# pca20020_sheet7_sound_and_light.net
KiCad netlist of a schematic drawn in Altium Designer
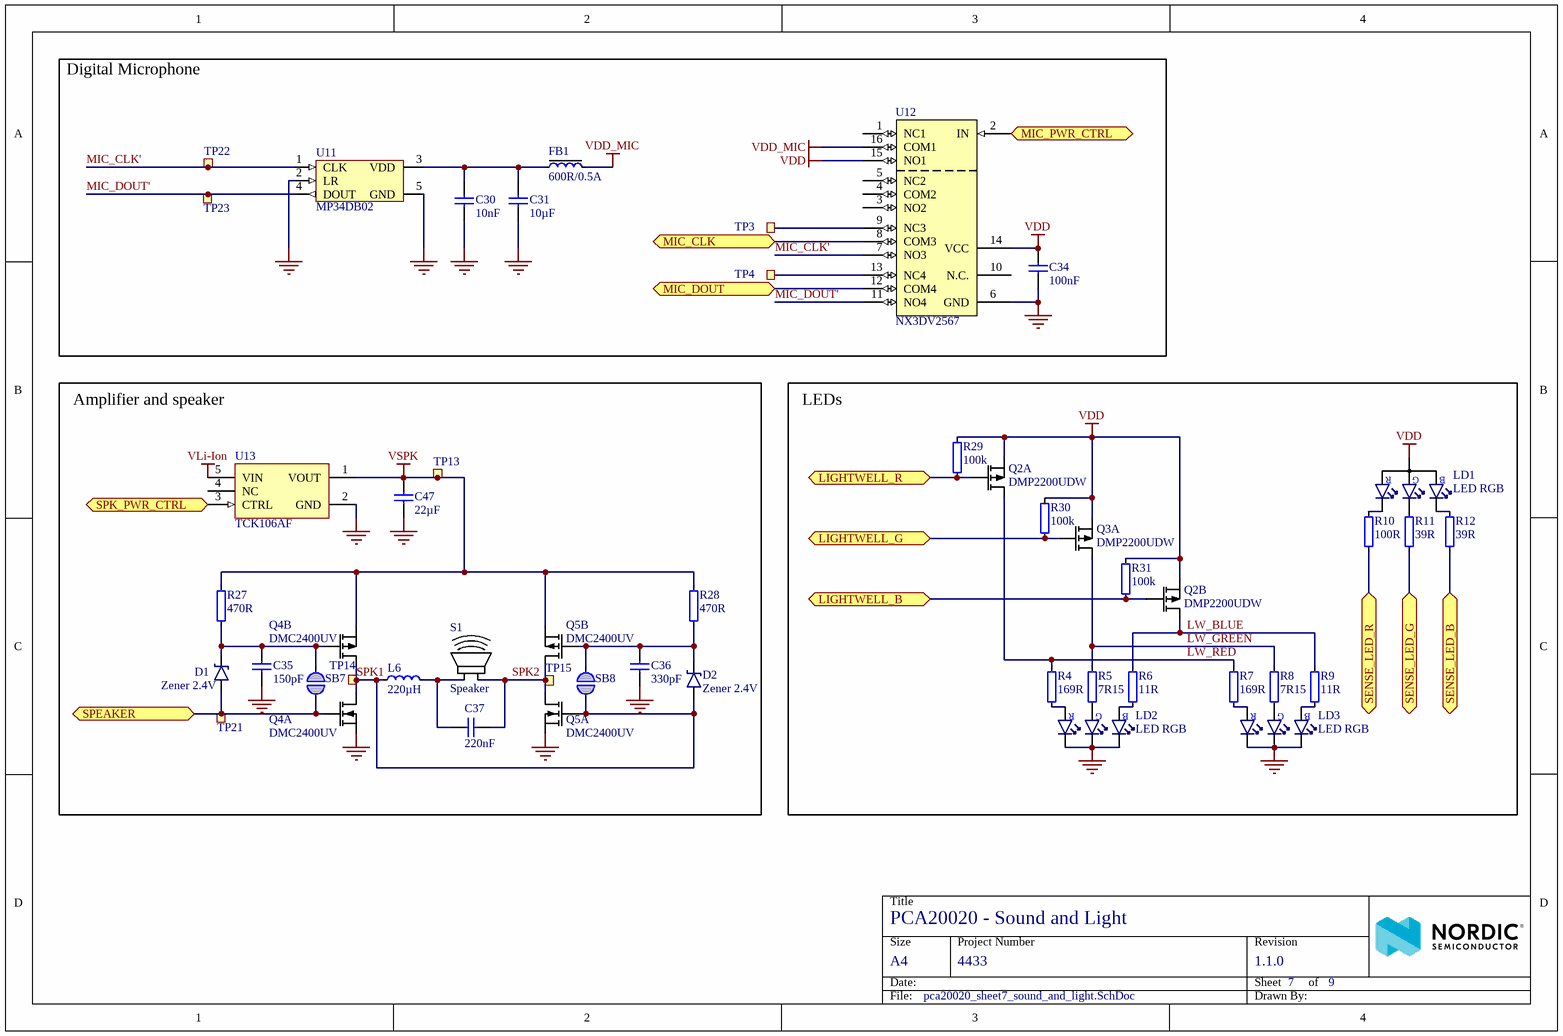
[diagram p0: pca20020_sheet7_sound_and_light.SchDoc]

(export (version "E")
  (design (tool "Eeschema 10.0.6"))
  (components
    (comp (ref "C30")
      (value "10nF")
      (footprint "CAPC1005X04L")
      (description "Capacitor, X7R, ±10%")
      (fields (field (name "PART NUMBER") "C0402-10n") (field (name "PUBLISHER") "Nordic Semiconductor"))
      (libsource (lib "Nordic Passive DB") (part "CAP"))
    )
    (comp (ref "C31")
      (value "10µF")
      (footprint "CAPC1608X06L")
      (description "Capacitor, X5R, ±20%")
      (fields (field (name "PART NUMBER") "C0603-10µ") (field (name "PUBLISHER") "Nordic Semiconductor"))
      (libsource (lib "Nordic Passive DB") (part "CAP"))
    )
    (comp (ref "C34")
      (value "100nF")
      (footprint "CAPC1005X04L")
      (description "Capacitor, X7R, ±10%")
      (fields (field (name "PART NUMBER") "C0402-100n") (field (name "PUBLISHER") "Nordic Semiconductor"))
      (libsource (lib "Nordic Passive DB") (part "CAP"))
    )
    (comp (ref "C35")
      (value "150pF")
      (footprint "CAPC1005X04L")
      (description "Capacitor, NP0, ±5%")
      (fields (field (name "PART NUMBER") "C0402-150p") (field (name "PUBLISHER") "Nordic Semiconductor"))
      (libsource (lib "Nordic Passive DB") (part "CAP"))
    )
    (comp (ref "C36")
      (value "330pF")
      (footprint "CAPC1005X04L")
      (description "Capacitor, NP0, ±5%")
      (fields (field (name "PART NUMBER") "C0402-330p") (field (name "PUBLISHER") "Nordic Semiconductor"))
      (libsource (lib "Nordic Passive DB") (part "CAP"))
    )
    (comp (ref "C37")
      (value "220nF")
      (footprint "CAPC1005X04L")
      (description "Capacitor, X7R, ±10%")
      (fields (field (name "PART NUMBER") "C0402-220n") (field (name "PUBLISHER") "Nordic Semiconductor"))
      (libsource (lib "Nordic Passive DB") (part "CAP"))
    )
    (comp (ref "C47")
      (value "22µF")
      (footprint "CAPC1608X06L")
      (description "CAP CER 22UF 6.3V 20% X5R 0603")
      (fields
        (field (name "PART NUMBER") "C0603-22µ-6.3V")
        (field (name "MANUFACTURER") "Samsung")
        (field (name "PUBLISHER") "Nordic Semiconductor")
      )
      (libsource (lib "Nordic Passive DB") (part "CAP"))
    )
    (comp (ref "D1")
      (value "Zener 2.4V")
      (footprint "SOD-523")
      (description "Diode, Zener, 2.4V, 0.3W")
      (fields
        (field (name "PART NUMBER") "BZT52C2V4T")
        (field (name "MANUFACTURER") "Diodes Incorporated")
        (field (name "PUBLISHER") "Nordic Semiconductor")
      )
      (libsource (lib "Nordic Discrete DB") (part "D{colon}ZENER"))
    )
    (comp (ref "D2")
      (value "Zener 2.4V")
      (footprint "SOD-523")
      (description "Diode, Zener, 2.4V, 0.3W")
      (fields
        (field (name "PART NUMBER") "BZT52C2V4T")
        (field (name "MANUFACTURER") "Diodes Incorporated")
        (field (name "PUBLISHER") "Nordic Semiconductor")
      )
      (libsource (lib "Nordic Discrete DB") (part "D{colon}ZENER"))
    )
    (comp (ref "FB1")
      (value "600R/0.5A")
      (footprint "INDC1608X06L")
      (description "Ferrite Bead, 600 Ohm @ 100MHz, 500mA, 380 mOhm Max")
      (fields
        (field (name "PART NUMBER") "FB0603-600R@100MHz-500mA")
        (field (name "MANUFACTURER") "Murata")
        (field (name "PUBLISHER") "Nordic Semiconductor")
      )
      (libsource (lib "Nordic Passive DB") (part "IND_F"))
    )
    (comp (ref "L6")
      (value "220µH")
      (footprint "INDP4040X25N")
      (description "Inductor, ±20%, 200mA, 2.76 Ohm")
      (fields
        (field (name "PART NUMBER") "L4040-220µ")
        (field (name "MANUFACTURER") "Bourns")
        (field (name "PUBLISHER") "Nordic Semiconductor")
      )
      (libsource (lib "Nordic Passive DB") (part "IND"))
    )
    (comp (ref "LD1")
      (value "LED RGB")
      (footprint "LED_RGB_0606")
      (description "RGB LED 1.60 mm x 1.60 mm SMD")
      (fields
        (field (name "PART NUMBER") "LTST-C19HE1WT")
        (field (name "MANUFACTURER") "Lite-On Inc")
        (field (name "PUBLISHER") "Nordic Semiconductor")
      )
      (libsource (lib "Nordic Discrete DB") (part "D{colon}LED_RGB"))
    )
    (comp (ref "LD2")
      (value "LED RGB")
      (footprint "MSL0104")
      (description "High brightness, side view RGB LED")
      (fields
        (field (name "PART NUMBER") "MSL0104RGBU1")
        (field (name "MANUFACTURER") "ROHM")
        (field (name "PUBLISHER") "Nordic Semiconductor")
      )
      (libsource (lib "Nordic Discrete DB") (part "D{colon}LED_RGB_MSL0104"))
    )
    (comp (ref "LD3")
      (value "LED RGB")
      (footprint "MSL0104")
      (description "High brightness, side view RGB LED")
      (fields
        (field (name "PART NUMBER") "MSL0104RGBU1")
        (field (name "MANUFACTURER") "ROHM")
        (field (name "PUBLISHER") "Nordic Semiconductor")
      )
      (libsource (lib "Nordic Discrete DB") (part "D{colon}LED_RGB_MSL0104"))
    )
    (comp (ref "Q2")
      (value "DMP2200UDW")
      (footprint "SOT-363")
      (description "Dual P Ch MOFET, 900mA, 260mOhm, 450mW")
      (fields
        (field (name "MANUFACTURER") "Diodes Incorporated")
        (field (name "PUBLISHER") "Nordic Semiconductor")
      )
      (libsource (lib "Nordic Discrete DB") (part "T{colon}FET-P-DUAL"))
    )
    (comp (ref "Q3")
      (value "DMP2200UDW")
      (footprint "SOT-363")
      (description "Dual P Ch MOFET, 900mA, 260mOhm, 450mW")
      (fields
        (field (name "MANUFACTURER") "Diodes Incorporated")
        (field (name "PUBLISHER") "Nordic Semiconductor")
      )
      (libsource (lib "Nordic Discrete DB") (part "T{colon}FET-P-DUAL"))
    )
    (comp (ref "Q4")
      (value "DMC2400UV")
      (footprint "SOTFL50P162X60-6N")
      (description "Dual N & P Ch MOFET, 1.03A/0.7A, 480mOhm, 450mW")
      (fields
        (field (name "MANUFACTURER") "Diodes Incorporated")
        (field (name "PUBLISHER") "Nordic Semiconductor")
      )
      (libsource (lib "Nordic Discrete DB") (part "T{colon}FET-N/P-DUAL"))
    )
    (comp (ref "Q5")
      (value "DMC2400UV")
      (footprint "SOTFL50P162X60-6N")
      (description "Dual N & P Ch MOFET, 1.03A/0.7A, 480mOhm, 450mW")
      (fields
        (field (name "MANUFACTURER") "Diodes Incorporated")
        (field (name "PUBLISHER") "Nordic Semiconductor")
      )
      (libsource (lib "Nordic Discrete DB") (part "T{colon}FET-N/P-DUAL"))
    )
    (comp (ref "R4")
      (value "169R")
      (footprint "RESC1005X04L")
      (description "Resistor, ±1%, 0.063W")
      (fields (field (name "PART NUMBER") "R0402-169") (field (name "PUBLISHER") "Nordic Semiconductor"))
      (libsource (lib "Nordic Passive DB") (part "RES_1"))
    )
    (comp (ref "R5")
      (value "7R15")
      (footprint "RESC1005X04L")
      (description "Resistor, ±1%, 0.063W")
      (fields (field (name "PART NUMBER") "R0402-7R15") (field (name "PUBLISHER") "Nordic Semiconductor"))
      (libsource (lib "Nordic Passive DB") (part "RES_1"))
    )
    (comp (ref "R6")
      (value "11R")
      (footprint "RESC1005X04L")
      (description "Resistor, ±1%, 0.063W")
      (fields (field (name "PART NUMBER") "R0402-11R") (field (name "PUBLISHER") "Nordic Semiconductor"))
      (libsource (lib "Nordic Passive DB") (part "RES_1"))
    )
    (comp (ref "R7")
      (value "169R")
      (footprint "RESC1005X04L")
      (description "Resistor, ±1%, 0.063W")
      (fields (field (name "PART NUMBER") "R0402-169") (field (name "PUBLISHER") "Nordic Semiconductor"))
      (libsource (lib "Nordic Passive DB") (part "RES_1"))
    )
    (comp (ref "R8")
      (value "7R15")
      (footprint "RESC1005X04L")
      (description "Resistor, ±1%, 0.063W")
      (fields (field (name "PART NUMBER") "R0402-7R15") (field (name "PUBLISHER") "Nordic Semiconductor"))
      (libsource (lib "Nordic Passive DB") (part "RES_1"))
    )
    (comp (ref "R9")
      (value "11R")
      (footprint "RESC1005X04L")
      (description "Resistor, ±1%, 0.063W")
      (fields (field (name "PART NUMBER") "R0402-11R") (field (name "PUBLISHER") "Nordic Semiconductor"))
      (libsource (lib "Nordic Passive DB") (part "RES_1"))
    )
    (comp (ref "R10")
      (value "100R")
      (footprint "RESC1005X04L")
      (description "Resistor, ±1%, 0.063W")
      (fields (field (name "PART NUMBER") "R0402-100") (field (name "PUBLISHER") "Nordic Semiconductor"))
      (libsource (lib "Nordic Passive DB") (part "RES_1"))
    )
    (comp (ref "R11")
      (value "39R")
      (footprint "RESC1005X04L")
      (description "Resistor, ±1%, 0.063W")
      (fields (field (name "PART NUMBER") "R0402-39R") (field (name "PUBLISHER") "Nordic Semiconductor"))
      (libsource (lib "Nordic Passive DB") (part "RES_1"))
    )
    (comp (ref "R12")
      (value "39R")
      (footprint "RESC1005X04L")
      (description "Resistor, ±1%, 0.063W")
      (fields (field (name "PART NUMBER") "R0402-39R") (field (name "PUBLISHER") "Nordic Semiconductor"))
      (libsource (lib "Nordic Passive DB") (part "RES_1"))
    )
    (comp (ref "R27")
      (value "470R")
      (footprint "RESC1005X04L")
      (description "Resistor, ±1%, 0.063W")
      (fields (field (name "PART NUMBER") "R0402-470") (field (name "PUBLISHER") "Nordic Semiconductor"))
      (libsource (lib "Nordic Passive DB") (part "RES_1"))
    )
    (comp (ref "R28")
      (value "470R")
      (footprint "RESC1005X04L")
      (description "Resistor, ±1%, 0.063W")
      (fields (field (name "PART NUMBER") "R0402-470") (field (name "PUBLISHER") "Nordic Semiconductor"))
      (libsource (lib "Nordic Passive DB") (part "RES_1"))
    )
    (comp (ref "R29")
      (value "100k")
      (footprint "RESC1005X04L")
      (description "Resistor, ±1%, 0.063W")
      (fields (field (name "PART NUMBER") "R0402-100k") (field (name "PUBLISHER") "Nordic Semiconductor"))
      (libsource (lib "Nordic Passive DB") (part "RES_1"))
    )
    (comp (ref "R30")
      (value "100k")
      (footprint "RESC1005X04L")
      (description "Resistor, ±1%, 0.063W")
      (fields (field (name "PART NUMBER") "R0402-100k") (field (name "PUBLISHER") "Nordic Semiconductor"))
      (libsource (lib "Nordic Passive DB") (part "RES_1"))
    )
    (comp (ref "R31")
      (value "100k")
      (footprint "RESC1005X04L")
      (description "Resistor, ±1%, 0.063W")
      (fields (field (name "PART NUMBER") "R0402-100k") (field (name "PUBLISHER") "Nordic Semiconductor"))
      (libsource (lib "Nordic Passive DB") (part "RES_1"))
    )
    (comp (ref "S1")
      (value "Speaker")
      (footprint "Speaker 15x11x3mm")
      (description "Speaker, SMD, 15.0mm x 11.0mm x 3.0mm, 0Hz-20kHz, 89dB, 8 ohm, 0.7W")
      (fields
        (field (name "PART NUMBER") "BMS1511F-11C-08H03P LF")
        (field (name "MANUFACTURER") "BeStar")
        (field (name "PUBLISHER") "Nordic Semiconductor")
      )
      (libsource (lib "Nordic Passive DB") (part "Speaker"))
    )
    (comp (ref "SB7")
      (value "Solderbridge")
      (footprint "Solderbridge")
      (fields (field (name "PUBLISHER") "Nordic Semiconductor"))
      (libsource (lib "Nordic Passive DB") (part "SOLDERBRIDGE"))
    )
    (comp (ref "SB8")
      (value "Solderbridge")
      (footprint "Solderbridge")
      (fields (field (name "PUBLISHER") "Nordic Semiconductor"))
      (libsource (lib "Nordic Passive DB") (part "SOLDERBRIDGE"))
    )
    (comp (ref "TP3")
      (value "TP")
      (footprint "TESTPAD-TH")
      (description "Testpoint, through hole")
      (fields (field (name "PART NUMBER") "Testpoint TH") (field (name "PUBLISHER") "Nordic Semiconductor"))
      (libsource (lib "") (part "TESTPAD_1"))
    )
    (comp (ref "TP4")
      (value "TP")
      (footprint "TESTPAD-TH")
      (description "Testpoint, through hole")
      (fields (field (name "PART NUMBER") "Testpoint TH") (field (name "PUBLISHER") "Nordic Semiconductor"))
      (libsource (lib "") (part "TESTPAD_1"))
    )
    (comp (ref "TP13")
      (value "Ø1.5mm,SMD")
      (footprint "TP_SMD_Ø1.5mm")
      (description "1.0mm circular SMD testpad")
      (fields
        (field (name "PART NUMBER") "TP_SMD_Ø1.5MM")
        (field (name "MANUFACTURER") "Nordic Semiconductor")
        (field (name "PUBLISHER") "Nordic Semiconductor")
      )
      (libsource (lib "") (part "TESTPAD_3"))
    )
    (comp (ref "TP14")
      (value "Ø1.5mm,SMD")
      (footprint "TP_SMD_Ø1.5mm")
      (description "1.0mm circular SMD testpad")
      (fields
        (field (name "PART NUMBER") "TP_SMD_Ø1.5MM")
        (field (name "MANUFACTURER") "Nordic Semiconductor")
        (field (name "PUBLISHER") "Nordic Semiconductor")
      )
      (libsource (lib "") (part "TESTPAD_1"))
    )
    (comp (ref "TP15")
      (value "Ø1.5mm,SMD")
      (footprint "TP_SMD_Ø1.5mm")
      (description "1.0mm circular SMD testpad")
      (fields
        (field (name "PART NUMBER") "TP_SMD_Ø1.5MM")
        (field (name "MANUFACTURER") "Nordic Semiconductor")
        (field (name "PUBLISHER") "Nordic Semiconductor")
      )
      (libsource (lib "") (part "TESTPAD_2"))
    )
    (comp (ref "TP21")
      (value "Ø1.5mm,SMD")
      (footprint "TP_SMD_Ø1.5mm")
      (description "1.0mm circular SMD testpad")
      (fields
        (field (name "PART NUMBER") "TP_SMD_Ø1.5MM")
        (field (name "MANUFACTURER") "Nordic Semiconductor")
        (field (name "PUBLISHER") "Nordic Semiconductor")
      )
      (libsource (lib "Nordic Passive DB") (part "TESTPAD"))
    )
    (comp (ref "TP22")
      (value "Ø1.5mm,SMD")
      (footprint "TP_SMD_Ø1.5mm")
      (description "1.0mm circular SMD testpad")
      (fields
        (field (name "PART NUMBER") "TP_SMD_Ø1.5MM")
        (field (name "MANUFACTURER") "Nordic Semiconductor")
        (field (name "PUBLISHER") "Nordic Semiconductor")
      )
      (libsource (lib "") (part "TESTPAD_3"))
    )
    (comp (ref "TP23")
      (value "Ø1.5mm,SMD")
      (footprint "TP_SMD_Ø1.5mm")
      (description "1.0mm circular SMD testpad")
      (fields
        (field (name "PART NUMBER") "TP_SMD_Ø1.5MM")
        (field (name "MANUFACTURER") "Nordic Semiconductor")
        (field (name "PUBLISHER") "Nordic Semiconductor")
      )
      (libsource (lib "Nordic Passive DB") (part "TESTPAD"))
    )
    (comp (ref "U11")
      (value "MP34DB02")
      (footprint "RHLGA-4 (3x4x1mm)")
      (description "MEMS audio sensor omnidirectional digital microphone")
      (fields
        (field (name "MANUFACTURER") "STMicroelectronics")
        (field (name "PUBLISHER") "Nordic Semiconductor")
      )
      (libsource (lib "Nordic Active DB") (part "DIG_MIC-5-pin"))
    )
    (comp (ref "U12")
      (value "NX3DV2567")
      (footprint "XQFN40P180X260X50-16N")
      (description "Low-ohmic four-pole double-throw analog switch")
      (fields
        (field (name "PART NUMBER") "NX3DV2567GU")
        (field (name "MANUFACTURER") "NXP Semiconductors")
        (field (name "PUBLISHER") "Nordic Semiconductor")
      )
      (libsource (lib "Nordic Active DB") (part "NX3DV2567"))
    )
    (comp (ref "U13")
      (value "TCK106AF")
      (footprint "SOT95P280X140-5N")
      (description "1.0 A Load Switch IC with Slew Rate Control Driver in Small Package")
      (fields
        (field (name "PART NUMBER") "TCK106AF,LF")
        (field (name "MANUFACTURER") "Toshiba")
        (field (name "PUBLISHER") "Nordic Semiconductor")
      )
      (libsource (lib "Nordic Active DB") (part "TCK10xAF"))
    )
  )
  (nets
    (net (code "1") (name "/LIGHTWELL_B") (class "Default")
      (node (ref "Q2") (pin "5") (pinfunction "G2_5") (pintype "passive"))
      (node (ref "R31") (pin "2") (pinfunction "2_2") (pintype "passive"))
    )
    (net (code "2") (name "/LIGHTWELL_G") (class "Default")
      (node (ref "Q3") (pin "2") (pinfunction "G1_2") (pintype "passive"))
      (node (ref "R30") (pin "2") (pinfunction "2_2") (pintype "passive"))
    )
    (net (code "3") (name "/LIGHTWELL_R") (class "Default")
      (node (ref "Q2") (pin "2") (pinfunction "G1_2") (pintype "passive"))
      (node (ref "R29") (pin "2") (pinfunction "2_2") (pintype "passive"))
    )
    (net (code "4") (name "/LW_BLUE") (class "Default")
      (node (ref "Q2") (pin "3") (pinfunction "D2_3") (pintype "passive"))
      (node (ref "R6") (pin "1") (pinfunction "1_1") (pintype "passive"))
      (node (ref "R9") (pin "1") (pinfunction "1_1") (pintype "passive"))
    )
    (net (code "5") (name "/LW_GREEN") (class "Default")
      (node (ref "Q3") (pin "6") (pinfunction "D1_6") (pintype "passive"))
      (node (ref "R5") (pin "1") (pinfunction "1_1") (pintype "passive"))
      (node (ref "R8") (pin "1") (pinfunction "1_1") (pintype "passive"))
    )
    (net (code "6") (name "/LW_RED") (class "Default")
      (node (ref "Q2") (pin "6") (pinfunction "D1_6") (pintype "passive"))
      (node (ref "R4") (pin "1") (pinfunction "1_1") (pintype "passive"))
      (node (ref "R7") (pin "1") (pinfunction "1_1") (pintype "passive"))
    )
    (net (code "7") (name "/MIC_CLK") (class "Default")
      (node (ref "U12") (pin "8") (pinfunction "COM3_8") (pintype "bidirectional"))
    )
    (net (code "8") (name "/MIC_CLK'") (class "Default")
      (node (ref "TP22") (pin "1") (pinfunction "1_1") (pintype "passive"))
      (node (ref "U11") (pin "1") (pinfunction "CLK_1") (pintype "input"))
      (node (ref "U12") (pin "7") (pinfunction "NO3_7") (pintype "bidirectional"))
    )
    (net (code "9") (name "/MIC_DOUT") (class "Default")
      (node (ref "U12") (pin "12") (pinfunction "COM4_12") (pintype "bidirectional"))
    )
    (net (code "10") (name "/MIC_DOUT'") (class "Default")
      (node (ref "TP23") (pin "1") (pinfunction "1_1") (pintype "passive"))
      (node (ref "U11") (pin "4") (pinfunction "DOUT_4") (pintype "output"))
      (node (ref "U12") (pin "11") (pinfunction "NO4_11") (pintype "bidirectional"))
    )
    (net (code "11") (name "/MIC_PWR_CTRL") (class "Default")
      (node (ref "U12") (pin "2") (pinfunction "IN_2") (pintype "input"))
    )
    (net (code "12") (name "/SENSE_LED_B") (class "Default")
      (node (ref "R12") (pin "1") (pinfunction "1_1") (pintype "passive"))
    )
    (net (code "13") (name "/SENSE_LED_G") (class "Default")
      (node (ref "R11") (pin "1") (pinfunction "1_1") (pintype "passive"))
    )
    (net (code "14") (name "/SENSE_LED_R") (class "Default")
      (node (ref "R10") (pin "1") (pinfunction "1_1") (pintype "passive"))
    )
    (net (code "15") (name "/SPEAKER") (class "Default")
      (node (ref "D1") (pin "1") (pinfunction "A_1") (pintype "passive"))
      (node (ref "Q4") (pin "2") (pinfunction "G1_2") (pintype "passive"))
      (node (ref "SB7") (pin "2") (pinfunction "1_2") (pintype "passive"))
      (node (ref "TP21") (pin "1") (pinfunction "1_1") (pintype "passive"))
    )
    (net (code "16") (name "/SPK1") (class "Default")
      (node (ref "D2") (pin "1") (pinfunction "A_1") (pintype "passive"))
      (node (ref "L6") (pin "1") (pinfunction "1_1") (pintype "passive"))
      (node (ref "Q4") (pin "3") (pinfunction "D2_3") (pintype "passive"))
      (node (ref "Q4") (pin "6") (pinfunction "D1_6") (pintype "passive"))
      (node (ref "Q5") (pin "2") (pinfunction "G1_2") (pintype "passive"))
      (node (ref "SB8") (pin "2") (pinfunction "1_2") (pintype "passive"))
      (node (ref "TP14") (pin "1") (pinfunction "1_1") (pintype "passive"))
    )
    (net (code "17") (name "/SPK2") (class "Default")
      (node (ref "C37") (pin "1") (pinfunction "1_1") (pintype "passive"))
      (node (ref "Q5") (pin "3") (pinfunction "D2_3") (pintype "passive"))
      (node (ref "Q5") (pin "6") (pinfunction "D1_6") (pintype "passive"))
      (node (ref "S1") (pin "2") (pinfunction "2_2") (pintype "passive"))
      (node (ref "TP15") (pin "1") (pinfunction "1_1") (pintype "passive"))
    )
    (net (code "18") (name "/SPK_PWR_CTRL") (class "Default")
      (node (ref "U13") (pin "3") (pinfunction "CTRL_3") (pintype "input"))
    )
    (net (code "19") (name "GND") (class "Default")
      (node (ref "C30") (pin "1") (pinfunction "1_1") (pintype "passive"))
      (node (ref "C31") (pin "1") (pinfunction "1_1") (pintype "passive"))
      (node (ref "C34") (pin "1") (pinfunction "1_1") (pintype "passive"))
      (node (ref "C35") (pin "1") (pinfunction "1_1") (pintype "passive"))
      (node (ref "C36") (pin "1") (pinfunction "1_1") (pintype "passive"))
      (node (ref "C47") (pin "1") (pinfunction "1_1") (pintype "passive"))
      (node (ref "LD2") (pin "3") (pinfunction "C_GREEN_3") (pintype "passive"))
      (node (ref "LD2") (pin "4") (pinfunction "C_RED_4") (pintype "passive"))
      (node (ref "LD2") (pin "5") (pinfunction "C_BLUE_5") (pintype "passive"))
      (node (ref "LD3") (pin "3") (pinfunction "C_GREEN_3") (pintype "passive"))
      (node (ref "LD3") (pin "4") (pinfunction "C_RED_4") (pintype "passive"))
      (node (ref "LD3") (pin "5") (pinfunction "C_BLUE_5") (pintype "passive"))
      (node (ref "Q4") (pin "1") (pinfunction "S1_1") (pintype "passive"))
      (node (ref "Q5") (pin "1") (pinfunction "S1_1") (pintype "passive"))
      (node (ref "U11") (pin "2") (pinfunction "LR_2") (pintype "input"))
      (node (ref "U11") (pin "5") (pinfunction "GND_5") (pintype "power_in"))
      (node (ref "U12") (pin "6") (pinfunction "GND_6") (pintype "power_in"))
      (node (ref "U13") (pin "2") (pinfunction "GND_2") (pintype "power_in"))
    )
    (net (code "20") (name "Net-(C37-Pad2)") (class "Default")
      (node (ref "C37") (pin "2") (pinfunction "2_2") (pintype "passive"))
      (node (ref "L6") (pin "2") (pinfunction "2_2") (pintype "passive"))
      (node (ref "S1") (pin "1") (pinfunction "1_1") (pintype "passive"))
    )
    (net (code "21") (name "Net-(D1-C)") (class "Default")
      (node (ref "C35") (pin "2") (pinfunction "2_2") (pintype "passive"))
      (node (ref "D1") (pin "3") (pinfunction "C_3") (pintype "passive"))
      (node (ref "Q4") (pin "5") (pinfunction "G2_5") (pintype "passive"))
      (node (ref "R27") (pin "2") (pinfunction "2_2") (pintype "passive"))
      (node (ref "SB7") (pin "1") (pinfunction "0_1") (pintype "passive"))
    )
    (net (code "22") (name "Net-(D2-C)") (class "Default")
      (node (ref "C36") (pin "2") (pinfunction "2_2") (pintype "passive"))
      (node (ref "D2") (pin "3") (pinfunction "C_3") (pintype "passive"))
      (node (ref "Q5") (pin "5") (pinfunction "G2_5") (pintype "passive"))
      (node (ref "R28") (pin "2") (pinfunction "2_2") (pintype "passive"))
      (node (ref "SB8") (pin "1") (pinfunction "0_1") (pintype "passive"))
    )
    (net (code "23") (name "Net-(LD1-C_BLUE)") (class "Default")
      (node (ref "LD1") (pin "3") (pinfunction "C_BLUE_3") (pintype "passive"))
      (node (ref "R12") (pin "2") (pinfunction "2_2") (pintype "passive"))
    )
    (net (code "24") (name "Net-(LD1-C_GREEN)") (class "Default")
      (node (ref "LD1") (pin "2") (pinfunction "C_GREEN_2") (pintype "passive"))
      (node (ref "R11") (pin "2") (pinfunction "2_2") (pintype "passive"))
    )
    (net (code "25") (name "Net-(LD1-C_RED)") (class "Default")
      (node (ref "LD1") (pin "1") (pinfunction "C_RED_1") (pintype "passive"))
      (node (ref "R10") (pin "2") (pinfunction "2_2") (pintype "passive"))
    )
    (net (code "26") (name "Net-(LD2-A_BLUE)") (class "Default")
      (node (ref "LD2") (pin "6") (pinfunction "A_BLUE_6") (pintype "passive"))
      (node (ref "R6") (pin "2") (pinfunction "2_2") (pintype "passive"))
    )
    (net (code "27") (name "Net-(LD2-A_GREEN)") (class "Default")
      (node (ref "LD2") (pin "2") (pinfunction "A_GREEN_2") (pintype "passive"))
      (node (ref "R5") (pin "2") (pinfunction "2_2") (pintype "passive"))
    )
    (net (code "28") (name "Net-(LD2-A_RED)") (class "Default")
      (node (ref "LD2") (pin "1") (pinfunction "A_RED_1") (pintype "passive"))
      (node (ref "R4") (pin "2") (pinfunction "2_2") (pintype "passive"))
    )
    (net (code "29") (name "Net-(LD3-A_BLUE)") (class "Default")
      (node (ref "LD3") (pin "6") (pinfunction "A_BLUE_6") (pintype "passive"))
      (node (ref "R9") (pin "2") (pinfunction "2_2") (pintype "passive"))
    )
    (net (code "30") (name "Net-(LD3-A_GREEN)") (class "Default")
      (node (ref "LD3") (pin "2") (pinfunction "A_GREEN_2") (pintype "passive"))
      (node (ref "R8") (pin "2") (pinfunction "2_2") (pintype "passive"))
    )
    (net (code "31") (name "Net-(LD3-A_RED)") (class "Default")
      (node (ref "LD3") (pin "1") (pinfunction "A_RED_1") (pintype "passive"))
      (node (ref "R7") (pin "2") (pinfunction "2_2") (pintype "passive"))
    )
    (net (code "32") (name "Net-(U11-VDD)") (class "Default")
      (node (ref "C30") (pin "2") (pinfunction "2_2") (pintype "passive"))
      (node (ref "C31") (pin "2") (pinfunction "2_2") (pintype "passive"))
      (node (ref "FB1") (pin "1") (pinfunction "1_1") (pintype "passive"))
      (node (ref "U11") (pin "3") (pinfunction "VDD_3") (pintype "power_in"))
    )
    (net (code "33") (name "Net-(U12-NC3)") (class "Default")
      (node (ref "TP3") (pin "1") (pinfunction "1_1") (pintype "passive"))
      (node (ref "U12") (pin "9") (pinfunction "NC3_9") (pintype "bidirectional"))
    )
    (net (code "34") (name "Net-(U12-NC4)") (class "Default")
      (node (ref "TP4") (pin "1") (pinfunction "1_1") (pintype "passive"))
      (node (ref "U12") (pin "13") (pinfunction "NC4_13") (pintype "bidirectional"))
    )
    (net (code "35") (name "VDD") (class "Default")
      (node (ref "C34") (pin "2") (pinfunction "2_2") (pintype "passive"))
      (node (ref "LD1") (pin "4") (pinfunction "A_4") (pintype "passive"))
      (node (ref "Q2") (pin "1") (pinfunction "S1_1") (pintype "passive"))
      (node (ref "Q2") (pin "4") (pinfunction "S2_4") (pintype "passive"))
      (node (ref "Q3") (pin "1") (pinfunction "S1_1") (pintype "passive"))
      (node (ref "R29") (pin "1") (pinfunction "1_1") (pintype "passive"))
      (node (ref "R30") (pin "1") (pinfunction "1_1") (pintype "passive"))
      (node (ref "R31") (pin "1") (pinfunction "1_1") (pintype "passive"))
      (node (ref "U12") (pin "14") (pinfunction "VCC_14") (pintype "power_in"))
      (node (ref "U12") (pin "15") (pinfunction "NO1_15") (pintype "bidirectional"))
    )
    (net (code "36") (name "VDD_MIC") (class "Default")
      (node (ref "FB1") (pin "2") (pinfunction "2_2") (pintype "passive"))
      (node (ref "U12") (pin "16") (pinfunction "COM1_16") (pintype "bidirectional"))
    )
    (net (code "37") (name "VLi-Ion") (class "Default")
      (node (ref "U13") (pin "5") (pinfunction "VIN_5") (pintype "power_in"))
    )
    (net (code "38") (name "VSPK") (class "Default")
      (node (ref "C47") (pin "2") (pinfunction "2_2") (pintype "passive"))
      (node (ref "Q4") (pin "4") (pinfunction "S2_4") (pintype "passive"))
      (node (ref "Q5") (pin "4") (pinfunction "S2_4") (pintype "passive"))
      (node (ref "R27") (pin "1") (pinfunction "1_1") (pintype "passive"))
      (node (ref "R28") (pin "1") (pinfunction "1_1") (pintype "passive"))
      (node (ref "TP13") (pin "1") (pinfunction "1_1") (pintype "passive"))
      (node (ref "U13") (pin "1") (pinfunction "VOUT_1") (pintype "power_in"))
    )
    (net (code "39") (name "unconnected-(U12-COM2-Pad4)") (class "Default")
      (node (ref "U12") (pin "4") (pinfunction "COM2_4") (pintype "bidirectional"))
    )
    (net (code "40") (name "unconnected-(U12-N.C.-Pad10)") (class "Default")
      (node (ref "U12") (pin "10") (pinfunction "N.C._10") (pintype "passive"))
    )
    (net (code "41") (name "unconnected-(U12-NC1-Pad1)") (class "Default")
      (node (ref "U12") (pin "1") (pinfunction "NC1_1") (pintype "bidirectional"))
    )
    (net (code "42") (name "unconnected-(U12-NC2-Pad5)") (class "Default")
      (node (ref "U12") (pin "5") (pinfunction "NC2_5") (pintype "bidirectional"))
    )
    (net (code "43") (name "unconnected-(U12-NO2-Pad3)") (class "Default")
      (node (ref "U12") (pin "3") (pinfunction "NO2_3") (pintype "bidirectional"))
    )
    (net (code "44") (name "unconnected-(U13-NC-Pad4)") (class "Default")
      (node (ref "U13") (pin "4") (pinfunction "NC_4") (pintype "passive"))
    )
  )
)
